# CON_MEZZANINE_GPIO.net
KiCad netlist of a schematic drawn in Altium Designer
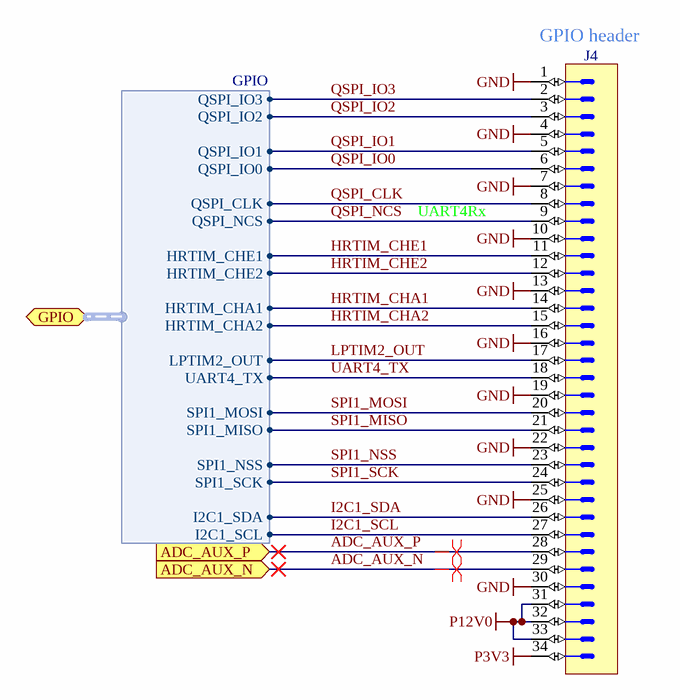
[diagram p0: CON_MEZZANINE_GPIO.SchDoc]

(export (version "E")
  (design (tool "Eeschema 10.0.6"))
  (components
    (comp (ref "J4")
      (value "Header 34")
      (footprint "3M_N2534-6002RB")
      (description "Connector 34 Male")
      (fields
        (field (name "PART NUMBER") "3M_N2534-6002RB")
        (field (name "MANUFACTURER") "3M")
        (field (name "AUTHOR") "CERN DEM JLC")
      )
      (libsource (lib "Connectors") (part "Connector 34 Male"))
    )
  )
  (nets
    (net (code "2") (name "/ADC_AUX_N") (class "Default")
      (node (ref "J4") (pin "29") (pinfunction "29_29") (pintype "bidirectional"))
    )
    (net (code "3") (name "/ADC_AUX_P") (class "Default")
      (node (ref "J4") (pin "28") (pinfunction "28_28") (pintype "bidirectional"))
    )
    (net (code "4") (name "/HRTIM_CHA1") (class "Default")
      (node (ref "J4") (pin "14") (pinfunction "14_14") (pintype "bidirectional"))
    )
    (net (code "5") (name "/HRTIM_CHA2") (class "Default")
      (node (ref "J4") (pin "15") (pinfunction "15_15") (pintype "bidirectional"))
    )
    (net (code "6") (name "/HRTIM_CHE1") (class "Default")
      (node (ref "J4") (pin "11") (pinfunction "11_11") (pintype "bidirectional"))
    )
    (net (code "7") (name "/HRTIM_CHE2") (class "Default")
      (node (ref "J4") (pin "12") (pinfunction "12_12") (pintype "bidirectional"))
    )
    (net (code "8") (name "/I2C1_SCL") (class "Default")
      (node (ref "J4") (pin "27") (pinfunction "27_27") (pintype "bidirectional"))
    )
    (net (code "9") (name "/I2C1_SDA") (class "Default")
      (node (ref "J4") (pin "26") (pinfunction "26_26") (pintype "bidirectional"))
    )
    (net (code "10") (name "/LPTIM2_OUT") (class "Default")
      (node (ref "J4") (pin "17") (pinfunction "17_17") (pintype "bidirectional"))
    )
    (net (code "11") (name "/QSPI_CLK") (class "Default")
      (node (ref "J4") (pin "8") (pinfunction "8_8") (pintype "bidirectional"))
    )
    (net (code "12") (name "/QSPI_IO0") (class "Default")
      (node (ref "J4") (pin "6") (pinfunction "6_6") (pintype "bidirectional"))
    )
    (net (code "13") (name "/QSPI_IO1") (class "Default")
      (node (ref "J4") (pin "5") (pinfunction "5_5") (pintype "bidirectional"))
    )
    (net (code "14") (name "/QSPI_IO2") (class "Default")
      (node (ref "J4") (pin "3") (pinfunction "3_3") (pintype "bidirectional"))
    )
    (net (code "15") (name "/QSPI_IO3") (class "Default")
      (node (ref "J4") (pin "2") (pinfunction "2_2") (pintype "bidirectional"))
    )
    (net (code "16") (name "/QSPI_NCS") (class "Default")
      (node (ref "J4") (pin "9") (pinfunction "9_9") (pintype "bidirectional"))
    )
    (net (code "17") (name "/SPI1_MISO") (class "Default")
      (node (ref "J4") (pin "21") (pinfunction "21_21") (pintype "bidirectional"))
    )
    (net (code "18") (name "/SPI1_MOSI") (class "Default")
      (node (ref "J4") (pin "20") (pinfunction "20_20") (pintype "bidirectional"))
    )
    (net (code "19") (name "/SPI1_NSS") (class "Default")
      (node (ref "J4") (pin "23") (pinfunction "23_23") (pintype "bidirectional"))
    )
    (net (code "20") (name "/SPI1_SCK") (class "Default")
      (node (ref "J4") (pin "24") (pinfunction "24_24") (pintype "bidirectional"))
    )
    (net (code "21") (name "/UART4_TX") (class "Default")
      (node (ref "J4") (pin "18") (pinfunction "18_18") (pintype "bidirectional"))
    )
    (net (code "23") (name "GND") (class "Default")
      (node (ref "J4") (pin "1") (pinfunction "1_1") (pintype "bidirectional"))
      (node (ref "J4") (pin "10") (pinfunction "10_10") (pintype "bidirectional"))
      (node (ref "J4") (pin "13") (pinfunction "13_13") (pintype "bidirectional"))
      (node (ref "J4") (pin "16") (pinfunction "16_16") (pintype "bidirectional"))
      (node (ref "J4") (pin "19") (pinfunction "19_19") (pintype "bidirectional"))
      (node (ref "J4") (pin "22") (pinfunction "22_22") (pintype "bidirectional"))
      (node (ref "J4") (pin "25") (pinfunction "25_25") (pintype "bidirectional"))
      (node (ref "J4") (pin "30") (pinfunction "30_30") (pintype "bidirectional"))
      (node (ref "J4") (pin "4") (pinfunction "4_4") (pintype "bidirectional"))
      (node (ref "J4") (pin "7") (pinfunction "7_7") (pintype "bidirectional"))
    )
    (net (code "24") (name "P3V3") (class "Default")
      (node (ref "J4") (pin "34") (pinfunction "34_34") (pintype "bidirectional"))
    )
    (net (code "25") (name "P12V0") (class "Default")
      (node (ref "J4") (pin "31") (pinfunction "31_31") (pintype "bidirectional"))
      (node (ref "J4") (pin "32") (pinfunction "32_32") (pintype "bidirectional"))
      (node (ref "J4") (pin "33") (pinfunction "33_33") (pintype "bidirectional"))
    )
  )
)
